# FTDI.net
KiCad netlist of a schematic drawn in Altium Designer
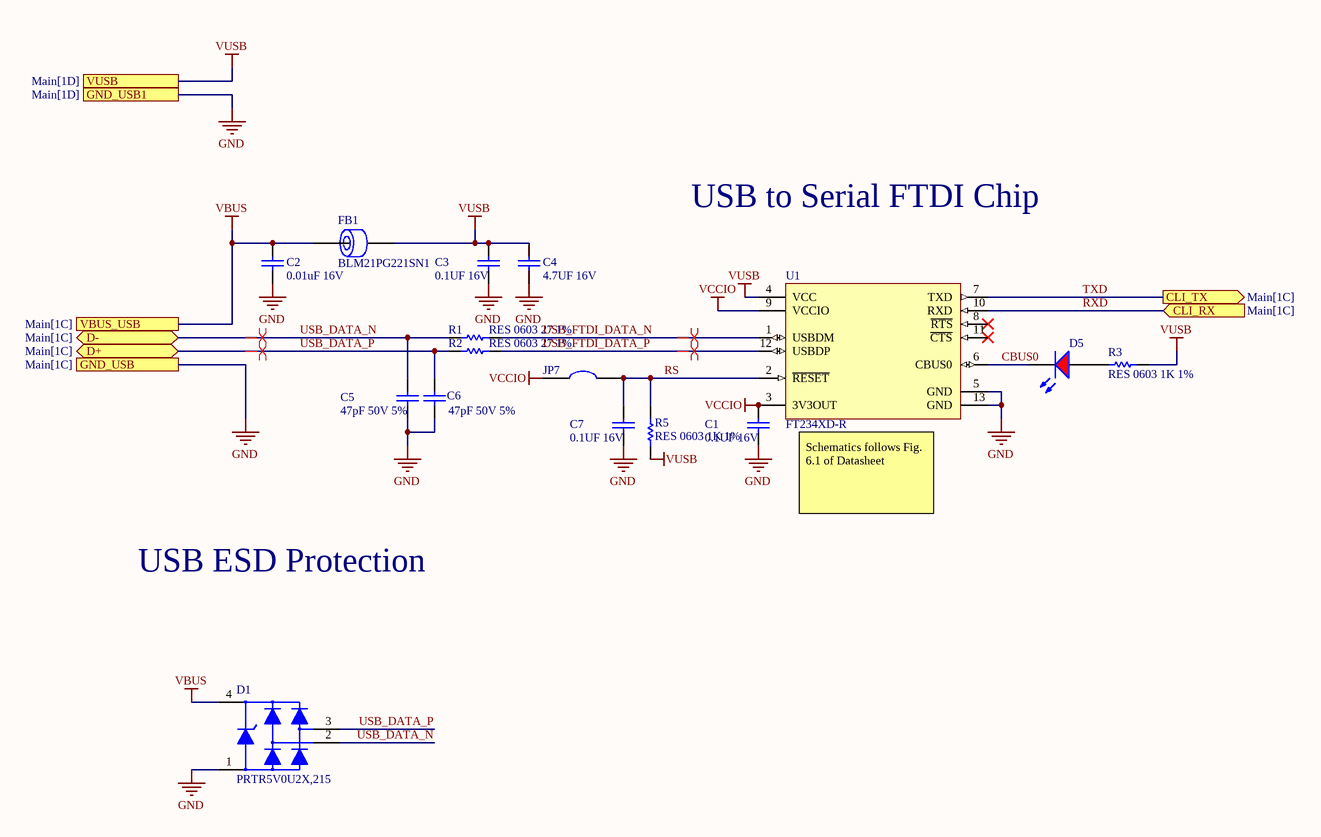
[diagram p0: FTDI.SchDoc]

(export (version "E")
  (design (tool "Eeschema 10.0.6"))
  (components
    (comp (ref "C1")
      (value "0.1UF 16V")
      (footprint "0603_CAP")
      (description "Capacitor Surface Mount 0603 Footprint 0.1UF 16V 10% Tolerance Ceramic X7R")
      (fields (field (name "VOLTAGE") "16V") (field (name "MANUFACTURER") "Various"))
      (libsource (lib "University of Pennsylvania (ESE Labs)") (part "cap"))
    )
    (comp (ref "C2")
      (value "0.01uF 16V")
      (footprint "0603_CAP")
      (description "Capacitor Surface Mount 0603 Footprint 0.01UF 16V 10% Tolerance Ceramic X7R")
      (fields (field (name "MANUFACTURER") "Various") (field (name "VOLTAGE") "16V"))
      (libsource (lib "University of Pennsylvania (ESE Labs)") (part "cap"))
    )
    (comp (ref "C3")
      (value "0.1UF 16V")
      (footprint "0603_CAP")
      (description "Capacitor Surface Mount 0603 Footprint 0.1UF 16V 10% Tolerance Ceramic X7R")
      (fields (field (name "VOLTAGE") "16V") (field (name "MANUFACTURER") "Various"))
      (libsource (lib "University of Pennsylvania (ESE Labs)") (part "cap"))
    )
    (comp (ref "C4")
      (value "4.7UF 16V")
      (footprint "0805_CAP")
      (description "Capacitor Surface Mount 0805 Footprint 4.7UF 16V 10% Tolerance Ceramic X7R")
      (fields (field (name "MANUFACTURER") "Various") (field (name "VOLTAGE") "16V"))
      (libsource (lib "University of Pennsylvania (ESE Labs)") (part "cap"))
    )
    (comp (ref "C5")
      (value "47pF 50V 5%")
      (footprint "0603_CAP")
      (description "Capacitor Surface Mount 0603 Footprint 47PF 50V 5% Tolerance Ceramic C0G")
      (fields (field (name "MANUFACTURER") "Various") (field (name "VOLTAGE") "50V"))
      (libsource (lib "University of Pennsylvania (ESE Labs)") (part "cap"))
    )
    (comp (ref "C6")
      (value "47pF 50V 5%")
      (footprint "0603_CAP")
      (description "Capacitor Surface Mount 0603 Footprint 47PF 50V 5% Tolerance Ceramic C0G")
      (fields (field (name "MANUFACTURER") "Various") (field (name "VOLTAGE") "50V"))
      (libsource (lib "University of Pennsylvania (ESE Labs)") (part "cap"))
    )
    (comp (ref "C7")
      (value "0.1UF 16V")
      (footprint "0603_CAP")
      (description "Capacitor Surface Mount 0603 Footprint 0.1UF 16V 10% Tolerance Ceramic X7R")
      (fields (field (name "VOLTAGE") "16V") (field (name "MANUFACTURER") "Various"))
      (libsource (lib "University of Pennsylvania (ESE Labs)") (part "cap"))
    )
    (comp (ref "D1")
      (value "PRTR5V0U2X,215")
      (footprint "FP-SOT143B-NXP")
      (description "Trans Voltage Suppressor Diode, 5.5V V(RWM), Unidirectional, 1 Element, Silicon")
      (libsource (lib "University of Pennsylvania (ESE Labs)") (part "PRTR5V0U2X,215-Symbol-1"))
    )
    (comp (ref "D5")
      (value "LSM0805412V")
      (footprint "LED_0805_RED")
      (description "Single Color LED, RED, 0805")
      (libsource (lib "University of Pennsylvania (ESE Labs)") (part "LED-RED-AK-2"))
    )
    (comp (ref "FB1")
      (value "BLM21PG221SN1")
      (footprint "0805")
      (description "Ferrite Chip 2000 mA 220 Ohms Differential Mode - Single 0805 Footprint")
      (fields (field (name "MANUFACTURER") "Murata"))
      (libsource (lib "University of Pennsylvania (ESE Labs)") (part "Ferrite Bead"))
    )
    (comp (ref "JP7")
      (value "0603 link")
      (footprint "0603_JP_RES")
      (description "0O link, SMD, 0603, Solder Bridge Option")
      (fields (field (name "MANUFACTURER") "Generic") (field (name "SOURCE") "Shunts and Jumpers.SchLib"))
      (libsource (lib "University of Pennsylvania (ESE)") (part "CMP-ROOT-0007-1"))
    )
    (comp (ref "R1")
      (value "RES 0603 27 1%")
      (footprint "0603_RES")
      (description "Resistor Surface Mount, 27 Ohms, 0603 Footprint, 1% Tolerance 0.1W")
      (fields (field (name "TOLERANCE") "1%") (field (name "MANUFACTURER") "Various"))
      (libsource (lib "University of Pennsylvania (ESE)") (part "res"))
    )
    (comp (ref "R2")
      (value "RES 0603 27 1%")
      (footprint "0603_RES")
      (description "Resistor Surface Mount, 27 Ohms, 0603 Footprint, 1% Tolerance 0.1W")
      (fields (field (name "TOLERANCE") "1%") (field (name "MANUFACTURER") "Various"))
      (libsource (lib "University of Pennsylvania (ESE)") (part "res"))
    )
    (comp (ref "R3")
      (value "RES 0603 1K 1%")
      (footprint "0603_RES")
      (description "Resistor Surface Mount, 1K Ohms, 0603 Footprint, 1% Tolerance 0.1W")
      (fields (field (name "MANUFACTURER") "Various") (field (name "TOLERANCE") "1%"))
      (libsource (lib "University of Pennsylvania (ESE)") (part "res"))
    )
    (comp (ref "R5")
      (value "RES 0603 1K 1%")
      (footprint "0603_RES")
      (description "Resistor Surface Mount, 1K Ohms, 0603 Footprint, 1% Tolerance 0.1W")
      (fields (field (name "MANUFACTURER") "Various") (field (name "TOLERANCE") "1%"))
      (libsource (lib "University of Pennsylvania (ESE)") (part "res"))
    )
    (comp (ref "U1")
      (value "FT234XD-R")
      (footprint "FP-DFN-12-MFG")
      (description "USB Bridge, USB to UART USB 2.0 UART Interface 12-DFN (3x3)")
      (libsource (lib "University of Pennsylvania (ESE)") (part "FT234-Symbol"))
    )
  )
  (nets
    (net (code "1") (name "/CBUS0") (class "Default")
      (node (ref "D5") (pin "K") (pinfunction "K_K") (pintype "passive"))
      (node (ref "U1") (pin "6") (pinfunction "CBUS0_6") (pintype "bidirectional"))
    )
    (net (code "2") (name "/RS") (class "Default")
      (node (ref "C7") (pin "2") (pinfunction "2_2") (pintype "passive"))
      (node (ref "JP7") (pin "2") (pinfunction "2_2") (pintype "passive"))
      (node (ref "R5") (pin "2") (pinfunction "2_2") (pintype "passive"))
      (node (ref "U1") (pin "2") (pinfunction "~{RESET}_2") (pintype "input"))
    )
    (net (code "3") (name "/RXD") (class "Default")
      (node (ref "U1") (pin "10") (pinfunction "RXD_10") (pintype "input"))
    )
    (net (code "4") (name "/TXD") (class "Default")
      (node (ref "U1") (pin "7") (pinfunction "TXD_7") (pintype "output"))
    )
    (net (code "5") (name "/USB_DATA_N") (class "Default")
      (node (ref "C5") (pin "2") (pinfunction "2_2") (pintype "passive"))
      (node (ref "D1") (pin "2") (pinfunction "2_2") (pintype "passive"))
      (node (ref "R1") (pin "1") (pinfunction "1_1") (pintype "passive"))
    )
    (net (code "6") (name "/USB_DATA_P") (class "Default")
      (node (ref "C6") (pin "2") (pinfunction "2_2") (pintype "passive"))
      (node (ref "D1") (pin "3") (pinfunction "3_3") (pintype "passive"))
      (node (ref "R2") (pin "1") (pinfunction "1_1") (pintype "passive"))
    )
    (net (code "7") (name "/USB_FTDI_DATA_N") (class "Default")
      (node (ref "R1") (pin "2") (pinfunction "2_2") (pintype "passive"))
      (node (ref "U1") (pin "1") (pinfunction "USBDM_1") (pintype "bidirectional"))
    )
    (net (code "8") (name "/USB_FTDI_DATA_P") (class "Default")
      (node (ref "R2") (pin "2") (pinfunction "2_2") (pintype "passive"))
      (node (ref "U1") (pin "12") (pinfunction "USBDP_12") (pintype "bidirectional"))
    )
    (net (code "9") (name "GND") (class "Default")
      (node (ref "C1") (pin "1") (pinfunction "1_1") (pintype "passive"))
      (node (ref "C2") (pin "1") (pinfunction "1_1") (pintype "passive"))
      (node (ref "C3") (pin "1") (pinfunction "1_1") (pintype "passive"))
      (node (ref "C4") (pin "1") (pinfunction "1_1") (pintype "passive"))
      (node (ref "C5") (pin "1") (pinfunction "1_1") (pintype "passive"))
      (node (ref "C6") (pin "1") (pinfunction "1_1") (pintype "passive"))
      (node (ref "C7") (pin "1") (pinfunction "1_1") (pintype "passive"))
      (node (ref "D1") (pin "1") (pinfunction "1_1") (pintype "passive"))
      (node (ref "U1") (pin "13") (pinfunction "GND_13") (pintype "power_in"))
      (node (ref "U1") (pin "5") (pinfunction "GND_5") (pintype "power_in"))
    )
    (net (code "10") (name "Net-(D5-PadA)") (class "Default")
      (node (ref "D5") (pin "A") (pinfunction "A_A") (pintype "passive"))
      (node (ref "R3") (pin "2") (pinfunction "2_2") (pintype "passive"))
    )
    (net (code "11") (name "VBUS") (class "Default")
      (node (ref "C2") (pin "2") (pinfunction "2_2") (pintype "passive"))
      (node (ref "D1") (pin "4") (pinfunction "4_4") (pintype "passive"))
      (node (ref "FB1") (pin "1") (pinfunction "1_1") (pintype "passive"))
    )
    (net (code "12") (name "VCCIO") (class "Default")
      (node (ref "C1") (pin "2") (pinfunction "2_2") (pintype "passive"))
      (node (ref "JP7") (pin "1") (pinfunction "1_1") (pintype "passive"))
      (node (ref "U1") (pin "3") (pinfunction "3V3OUT_3") (pintype "power_in"))
      (node (ref "U1") (pin "9") (pinfunction "VCCIO_9") (pintype "power_in"))
    )
    (net (code "13") (name "VUSB") (class "Default")
      (node (ref "C3") (pin "2") (pinfunction "2_2") (pintype "passive"))
      (node (ref "C4") (pin "2") (pinfunction "2_2") (pintype "passive"))
      (node (ref "FB1") (pin "2") (pinfunction "2_2") (pintype "passive"))
      (node (ref "R3") (pin "1") (pinfunction "1_1") (pintype "passive"))
      (node (ref "R5") (pin "1") (pinfunction "1_1") (pintype "passive"))
      (node (ref "U1") (pin "4") (pinfunction "VCC_4") (pintype "power_in"))
    )
    (net (code "14") (name "unconnected-(U1-~{CTS}-Pad11)") (class "Default")
      (node (ref "U1") (pin "11") (pinfunction "~{CTS}_11") (pintype "input+no_connect"))
    )
    (net (code "15") (name "unconnected-(U1-~{RTS}-Pad8)") (class "Default")
      (node (ref "U1") (pin "8") (pinfunction "~{RTS}_8") (pintype "input+no_connect"))
    )
  )
)
